# 4_POW_schdoc.net
KiCad netlist of a schematic drawn in Altium Designer
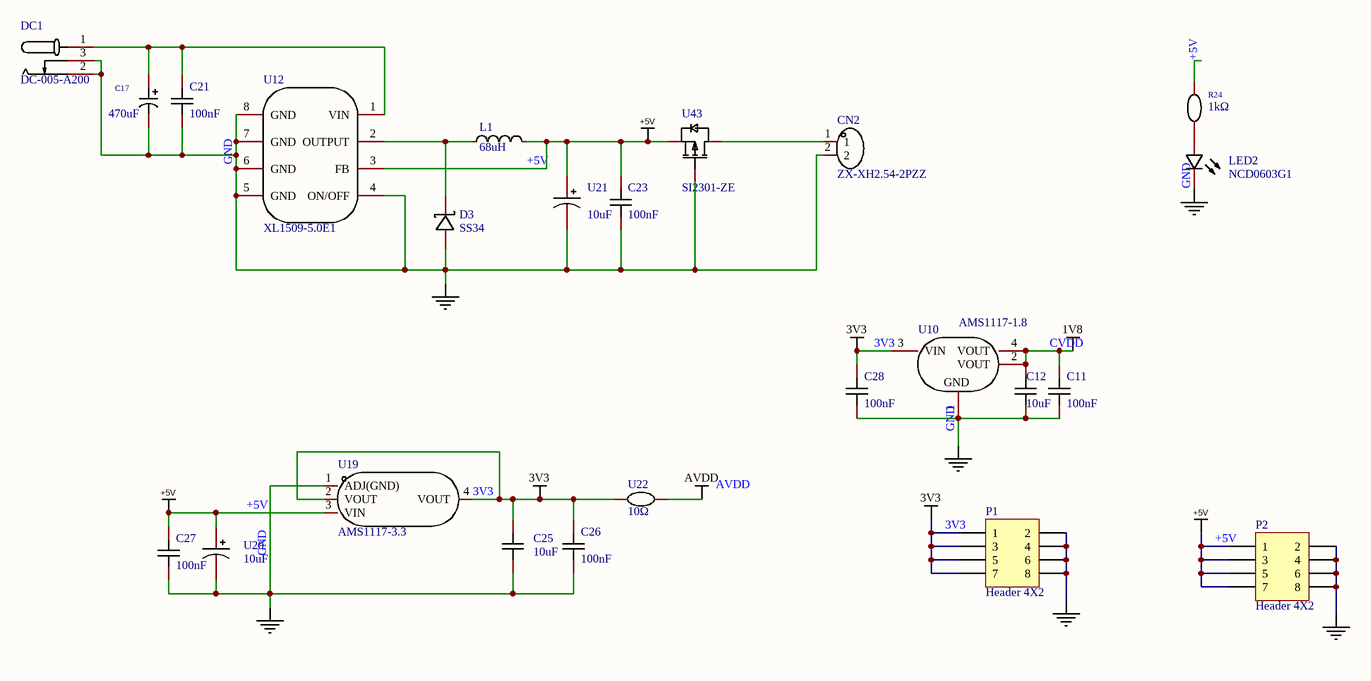
[diagram p0: 4_POW.schdoc.schdoc]

(export (version "E")
  (design (tool "Eeschema 10.0.6"))
  (components
    (comp (ref "C11")
      (value "100nF")
      (footprint "C0603")
      (description "容值:100nF;精度:±20%;额定电压:50V;材质(温度系数):X8R;")
      (fields
        (field (name "NAME") "100nF")
        (field (name "MANUFACTURER") "TDK")
        (field (name "MANUFACTURER PART") "CGA3E3X8R1H104M080AE")
      )
      (libsource (lib "altium-import") (part "root_1_CGA3E3X8R1H104M080AE_"))
    )
    (comp (ref "C12")
      (value "10uF")
      (footprint "C0603")
      (description "容值:10uF;精度:±20%;额定电压:6.3V;材质(温度系数):X6S;")
      (fields
        (field (name "NAME") "10uF")
        (field (name "MANUFACTURER") "TDK")
        (field (name "MANUFACTURER PART") "C1608X6S0J106M080AC")
      )
      (libsource (lib "altium-import") (part "root_1_C1608X6S0J106M080AC_"))
    )
    (comp (ref "C17")
      (value "470uF")
      (footprint "CAP-SMD_BD6.3-L6.6-W6.6-LS7.6-RD")
      (description "容值:470uF;精度:±20%;额定电压:16V;电容体直径:6.3mm;电容体长度:7.7mm;工作寿命:2000hrs@105℃;工作温度:-55℃~+105℃;")
      (fields
        (field (name "NAME") "470uF")
        (field (name "MANUFACTURER") "ROQANG(容强)")
        (field (name "MANUFACTURER PART") "RVT1C471M0607")
      )
      (libsource (lib "altium-import") (part "root_3_RVT1C471M0607_"))
    )
    (comp (ref "C21")
      (value "100nF")
      (footprint "C0603")
      (description "容值:100nF;精度:±20%;额定电压:50V;材质(温度系数):X8R;")
      (fields
        (field (name "NAME") "100nF")
        (field (name "MANUFACTURER") "TDK")
        (field (name "MANUFACTURER PART") "CGA3E3X8R1H104M080AE")
      )
      (libsource (lib "altium-import") (part "root_1_CGA3E3X8R1H104M080AE_"))
    )
    (comp (ref "C23")
      (value "100nF")
      (footprint "C0603")
      (description "容值:100nF;精度:±20%;额定电压:50V;材质(温度系数):X8R;")
      (fields
        (field (name "NAME") "100nF")
        (field (name "MANUFACTURER") "TDK")
        (field (name "MANUFACTURER PART") "CGA3E3X8R1H104M080AE")
      )
      (libsource (lib "altium-import") (part "root_1_CGA3E3X8R1H104M080AE_"))
    )
    (comp (ref "C25")
      (value "10uF")
      (footprint "C0603")
      (description "容值:10uF;精度:±20%;额定电压:6.3V;材质(温度系数):X6S;")
      (fields
        (field (name "NAME") "10uF")
        (field (name "MANUFACTURER") "TDK")
        (field (name "MANUFACTURER PART") "C1608X6S0J106M080AC")
      )
      (libsource (lib "altium-import") (part "root_1_C1608X6S0J106M080AC_"))
    )
    (comp (ref "C26")
      (value "100nF")
      (footprint "C0603")
      (description "容值:100nF;精度:±20%;额定电压:50V;材质(温度系数):X8R;")
      (fields
        (field (name "NAME") "100nF")
        (field (name "MANUFACTURER") "TDK")
        (field (name "MANUFACTURER PART") "CGA3E3X8R1H104M080AE")
      )
      (libsource (lib "altium-import") (part "root_1_CGA3E3X8R1H104M080AE_"))
    )
    (comp (ref "C27")
      (value "100nF")
      (footprint "C0603")
      (description "容值:100nF;精度:±20%;额定电压:50V;材质(温度系数):X8R;")
      (fields
        (field (name "NAME") "100nF")
        (field (name "MANUFACTURER") "TDK")
        (field (name "MANUFACTURER PART") "CGA3E3X8R1H104M080AE")
      )
      (libsource (lib "altium-import") (part "root_1_CGA3E3X8R1H104M080AE_"))
    )
    (comp (ref "C28")
      (value "100nF")
      (footprint "C0603")
      (description "容值:100nF;精度:±20%;额定电压:50V;材质(温度系数):X8R;")
      (fields
        (field (name "NAME") "100nF")
        (field (name "MANUFACTURER") "TDK")
        (field (name "MANUFACTURER PART") "CGA3E3X8R1H104M080AE")
      )
      (libsource (lib "altium-import") (part "root_1_CGA3E3X8R1H104M080AE_"))
    )
    (comp (ref "CN2")
      (value "ZX-XH2.54-2PZZ")
      (footprint "CONN-TH_2P-P2.50_HX25003-2A")
      (fields (field (name "NAME") "ZX-XH2.54-2PZZ") (field (name "MANUFACTURER") "Megastar(兆星)"))
      (libsource (lib "altium-import") (part "root_0_ZX-XH2.54-2PZZ_"))
    )
    (comp (ref "D3")
      (value "SS34")
      (footprint "SMA_L4.3-W2.6-LS5.0-RD")
      (fields (field (name "NAME") "SS34"))
      (libsource (lib "altium-import") (part "root_3_SS34_"))
    )
    (comp (ref "DC1")
      (value "DC-005-A200")
      (footprint "DC-IN-TH_DC-005-A200")
      (description "DC-005 外径6.4 内芯2.0 3A电流 DC电源插座")
      (fields (field (name "NAME") "DC-005-A200") (field (name "MANUFACTURER") "XUNPU(讯普)"))
      (libsource (lib "altium-import") (part "root_0_DC-005-A200_"))
    )
    (comp (ref "L1")
      (value "68uH")
      (footprint "IND-SMD_L6.0-W6.0_SWPA6045S")
      (description "类型:-;电感值:68uH;精度:±20%;额定电流:1A;饱和电流(Isat):1.2A;")
      (fields
        (field (name "NAME") "68uH")
        (field (name "MANUFACTURER") "Sunlord(顺络)")
        (field (name "MANUFACTURER PART") "SWPA6045S680MT")
      )
      (libsource (lib "altium-import") (part "root_0_SWPA6045S680MT_"))
    )
    (comp (ref "LED2")
      (value "NCD0603G1")
      (footprint "LED0603-RD")
      (description "发光颜色:翠绿色;功率:72mW;透镜颜色:无色透明;主波长:515nm~530nm;发光强度:330mcd~900mcd;发光角度:130°;工作温度:-30℃~+85℃;")
      (fields (field (name "NAME") "NCD0603G1") (field (name "MANUFACTURER") "国星光电"))
      (libsource (lib "altium-import") (part "root_3_NCD0603G1_"))
    )
    (comp (ref "P1")
      (value "Header 4X2")
      (footprint "HDR2X4")
      (description "Header, 4-Pin, Dual row")
      (fields (field (name "PUBLISHER") "Altium Limited"))
      (libsource (lib "Miscellaneous Connectors") (part "Header 4X2"))
    )
    (comp (ref "P2")
      (value "Header 4X2")
      (footprint "HDR2X4")
      (description "Header, 4-Pin, Dual row")
      (fields (field (name "PUBLISHER") "Altium Limited"))
      (libsource (lib "Miscellaneous Connectors") (part "Header 4X2"))
    )
    (comp (ref "R24")
      (value "1kΩ")
      (footprint "R0603")
      (description "阻值:1kΩ;精度:±1%;")
      (fields
        (field (name "NAME") "1kΩ")
        (field (name "MANUFACTURER") "VO(翔胜)")
        (field (name "MANUFACTURER PART") "SCR0603F1K")
      )
      (libsource (lib "altium-import") (part "root_1_SCR0603F1K_"))
    )
    (comp (ref "U10")
      (value "AMS1117-1.8")
      (footprint "SOT-223-4_L6.5-W3.5-P2.30-LS7.0-BR")
      (description "输出类型:固定;输出极性:正;最大输入电压:18V;输出电压:1.8V;输出电流:1A;电源纹波抑制比(PSRR):-;")
      (fields (field (name "NAME") "AMS1117-1.8") (field (name "MANUFACTURER") "PUOLOP(迪浦)"))
      (libsource (lib "altium-import") (part "root_0_AMS1117-1.8_"))
    )
    (comp (ref "U12")
      (value "XL1509-5.0E1")
      (footprint "SOIC-8_L5.0-W4.0-P1.27-LS6.0-BL")
      (description "功能类型:降压型;输入电压:-;输出电流(最大值):-;")
      (fields (field (name "NAME") "XL1509-5.0E1") (field (name "MANUFACTURER") "XLSEMI(芯龙)"))
      (libsource (lib "altium-import") (part "root_0_mirrored_XL1509-5.0E1_"))
    )
    (comp (ref "U19")
      (value "AMS1117-3.3")
      (footprint "SOT-223-3_L6.5-W3.4-P2.30-LS7.0-BR")
      (fields (field (name "NAME") "AMS1117-3.3") (field (name "MANUFACTURER") "YONGYUTAI(永裕泰)"))
      (libsource (lib "altium-import") (part "root_0_AMS1117-3.3_"))
    )
    (comp (ref "U20")
      (value "10uF")
      (footprint "CAP-TH_BD6.3-P2.50-D0.5-FD")
      (description "容值:10uF;精度:±20%;额定电压:50V;纹波电流:-;等效串联电阻:-;")
      (fields
        (field (name "NAME") "10uF")
        (field (name "MANUFACTURER") "MAN YUE(万裕科技)")
        (field (name "MANUFACTURER PART") "ESK106M1HD11RRSNP-R")
      )
      (libsource (lib "altium-import") (part "root_3_ESK106M1HD11RRSNP-R_"))
    )
    (comp (ref "U21")
      (value "10uF")
      (footprint "CAP-TH_BD6.3-P2.50-D0.5-FD")
      (description "容值:10uF;精度:±20%;额定电压:50V;纹波电流:-;等效串联电阻:-;")
      (fields
        (field (name "NAME") "10uF")
        (field (name "MANUFACTURER") "MAN YUE(万裕科技)")
        (field (name "MANUFACTURER PART") "ESK106M1HD11RRSNP-R")
      )
      (libsource (lib "altium-import") (part "root_3_ESK106M1HD11RRSNP-R_"))
    )
    (comp (ref "U22")
      (value "10Ω")
      (footprint "R0603")
      (description "电阻类型:薄膜电阻;阻值:10Ω;精度:±0.1%;功率:500mW;")
      (fields
        (field (name "NAME") "10Ω")
        (field (name "MANUFACTURER") "VISHAY(威世)")
        (field (name "MANUFACTURER PART") "PCAN0603E10R0BST5")
      )
      (libsource (lib "altium-import") (part "root_0_PCAN0603E10R0BST5_"))
    )
    (comp (ref "U43")
      (value "SI2301-ZE")
      (footprint "SOT-23-3_L2.9-W1.3-P1.90-LS2.4-BR")
      (description "漏源电压(Vdss):20V;连续漏极电流(Id):2.3A;功率(Pd):700mW;类型:P沟道;导通电阻(RDS(on)@Vgs,Id):126mΩ@4.5V;")
      (fields (field (name "NAME") "SI2301-ZE") (field (name "MANUFACTURER") "HXY MOSFET(华轩阳电子)"))
      (libsource (lib "altium-import") (part "root_1_mirrored_SI2301-ZE_"))
    )
  )
  (nets
    (net (code "1") (name "+5V") (class "Default")
      (node (ref "C23") (pin "2") (pinfunction "2_2") (pintype "passive"))
      (node (ref "C27") (pin "2") (pinfunction "2_2") (pintype "passive"))
      (node (ref "L1") (pin "2") (pinfunction "2_2") (pintype "passive"))
      (node (ref "P2") (pin "1") (pinfunction "1_1") (pintype "passive"))
      (node (ref "P2") (pin "3") (pinfunction "3_3") (pintype "passive"))
      (node (ref "P2") (pin "5") (pinfunction "5_5") (pintype "passive"))
      (node (ref "P2") (pin "7") (pinfunction "7_7") (pintype "passive"))
      (node (ref "R24") (pin "2") (pinfunction "2_2") (pintype "passive"))
      (node (ref "U12") (pin "3") (pinfunction "FB_3") (pintype "passive"))
      (node (ref "U19") (pin "3") (pinfunction "VIN_3") (pintype "passive"))
      (node (ref "U20") (pin "1") (pinfunction "1_1") (pintype "passive"))
      (node (ref "U21") (pin "1") (pinfunction "1_1") (pintype "passive"))
      (node (ref "U43") (pin "2") (pinfunction "S_2") (pintype "passive"))
    )
    (net (code "2") (name "/GND") (class "Default")
      (node (ref "C11") (pin "1") (pinfunction "1_1") (pintype "passive"))
      (node (ref "C12") (pin "1") (pinfunction "1_1") (pintype "passive"))
      (node (ref "C17") (pin "2") (pinfunction "2_2") (pintype "passive"))
      (node (ref "C21") (pin "1") (pinfunction "1_1") (pintype "passive"))
      (node (ref "C23") (pin "1") (pinfunction "1_1") (pintype "passive"))
      (node (ref "C25") (pin "1") (pinfunction "1_1") (pintype "passive"))
      (node (ref "C26") (pin "1") (pinfunction "1_1") (pintype "passive"))
      (node (ref "C27") (pin "1") (pinfunction "1_1") (pintype "passive"))
      (node (ref "C28") (pin "1") (pinfunction "1_1") (pintype "passive"))
      (node (ref "CN2") (pin "2") (pinfunction "2_2") (pintype "passive"))
      (node (ref "D3") (pin "2") (pinfunction "A_2") (pintype "passive"))
      (node (ref "DC1") (pin "2") (pinfunction "2_2") (pintype "passive"))
      (node (ref "DC1") (pin "3") (pinfunction "3_3") (pintype "passive"))
      (node (ref "LED2") (pin "1") (pinfunction "K_1") (pintype "passive"))
      (node (ref "P1") (pin "2") (pinfunction "2_2") (pintype "passive"))
      (node (ref "P1") (pin "4") (pinfunction "4_4") (pintype "passive"))
      (node (ref "P1") (pin "6") (pinfunction "6_6") (pintype "passive"))
      (node (ref "P1") (pin "8") (pinfunction "8_8") (pintype "passive"))
      (node (ref "P2") (pin "2") (pinfunction "2_2") (pintype "passive"))
      (node (ref "P2") (pin "4") (pinfunction "4_4") (pintype "passive"))
      (node (ref "P2") (pin "6") (pinfunction "6_6") (pintype "passive"))
      (node (ref "P2") (pin "8") (pinfunction "8_8") (pintype "passive"))
      (node (ref "U10") (pin "1") (pinfunction "GND_1") (pintype "passive"))
      (node (ref "U12") (pin "4") (pinfunction "ON/OFF_4") (pintype "passive"))
      (node (ref "U12") (pin "5") (pinfunction "GND_5") (pintype "passive"))
      (node (ref "U12") (pin "6") (pinfunction "GND_6") (pintype "passive"))
      (node (ref "U12") (pin "7") (pinfunction "GND_7") (pintype "passive"))
      (node (ref "U12") (pin "8") (pinfunction "GND_8") (pintype "passive"))
      (node (ref "U19") (pin "1") (pinfunction "ADJ(GND)_1") (pintype "passive"))
      (node (ref "U20") (pin "2") (pinfunction "2_2") (pintype "passive"))
      (node (ref "U21") (pin "2") (pinfunction "2_2") (pintype "passive"))
      (node (ref "U43") (pin "1") (pinfunction "G_1") (pintype "passive"))
    )
    (net (code "3") (name "1V8") (class "Default")
      (node (ref "C11") (pin "2") (pinfunction "2_2") (pintype "passive"))
      (node (ref "C12") (pin "2") (pinfunction "2_2") (pintype "passive"))
      (node (ref "U10") (pin "2") (pinfunction "VOUT_2") (pintype "passive"))
      (node (ref "U10") (pin "4") (pinfunction "VOUT_4") (pintype "passive"))
    )
    (net (code "4") (name "3V3") (class "Default")
      (node (ref "C25") (pin "2") (pinfunction "2_2") (pintype "passive"))
      (node (ref "C26") (pin "2") (pinfunction "2_2") (pintype "passive"))
      (node (ref "C28") (pin "2") (pinfunction "2_2") (pintype "passive"))
      (node (ref "P1") (pin "1") (pinfunction "1_1") (pintype "passive"))
      (node (ref "P1") (pin "3") (pinfunction "3_3") (pintype "passive"))
      (node (ref "P1") (pin "5") (pinfunction "5_5") (pintype "passive"))
      (node (ref "P1") (pin "7") (pinfunction "7_7") (pintype "passive"))
      (node (ref "U10") (pin "3") (pinfunction "VIN_3") (pintype "passive"))
      (node (ref "U19") (pin "2") (pinfunction "VOUT_2") (pintype "passive"))
      (node (ref "U19") (pin "4") (pinfunction "VOUT_4") (pintype "passive"))
      (node (ref "U22") (pin "1") (pinfunction "1_1") (pintype "passive"))
    )
    (net (code "5") (name "AVDD") (class "Default")
      (node (ref "U22") (pin "2") (pinfunction "2_2") (pintype "passive"))
    )
    (net (code "6") (name "Net-(D3-K)") (class "Default")
      (node (ref "D3") (pin "1") (pinfunction "K_1") (pintype "passive"))
      (node (ref "L1") (pin "1") (pinfunction "1_1") (pintype "passive"))
      (node (ref "U12") (pin "2") (pinfunction "OUTPUT_2") (pintype "passive"))
    )
    (net (code "7") (name "Net-(LED2-A)") (class "Default")
      (node (ref "LED2") (pin "2") (pinfunction "A_2") (pintype "passive"))
      (node (ref "R24") (pin "1") (pinfunction "1_1") (pintype "passive"))
    )
    (net (code "8") (name "Net-(U12-VIN)") (class "Default")
      (node (ref "C17") (pin "1") (pinfunction "1_1") (pintype "passive"))
      (node (ref "C21") (pin "2") (pinfunction "2_2") (pintype "passive"))
      (node (ref "DC1") (pin "1") (pinfunction "1_1") (pintype "passive"))
      (node (ref "U12") (pin "1") (pinfunction "VIN_1") (pintype "passive"))
    )
    (net (code "9") (name "Net-(U43-D)") (class "Default")
      (node (ref "CN2") (pin "1") (pinfunction "1_1") (pintype "passive"))
      (node (ref "U43") (pin "3") (pinfunction "D_3") (pintype "passive"))
    )
  )
)
